# STM32.net
KiCad netlist of a schematic drawn in Altium Designer
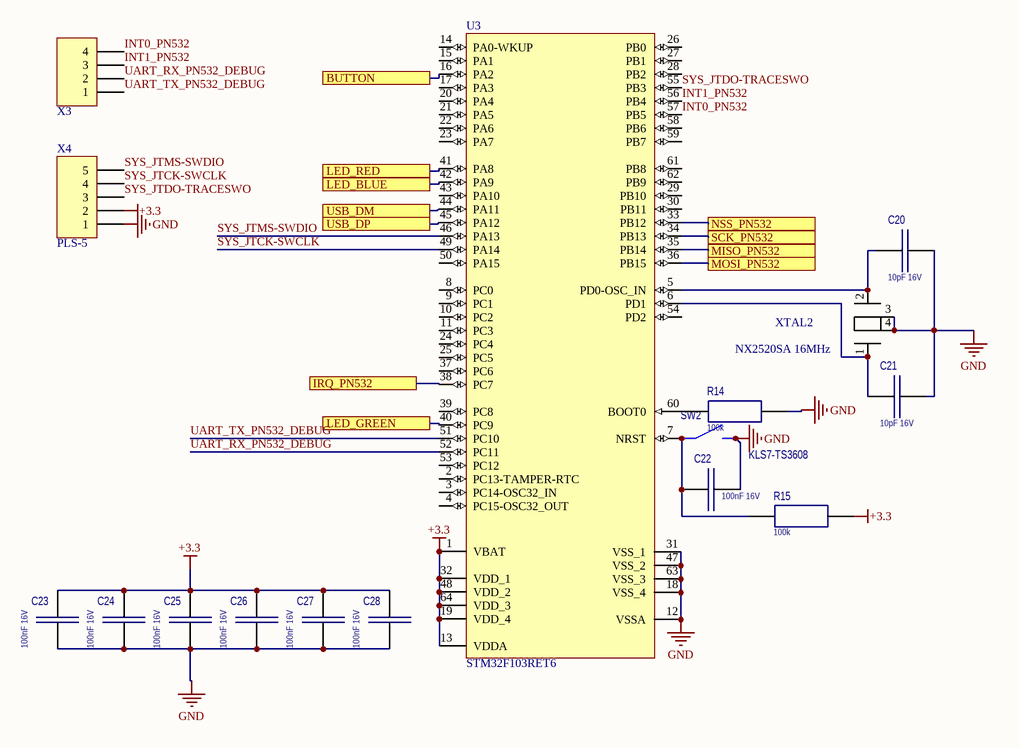
[diagram p0: STM32.SchDoc]

(export (version "E")
  (design (tool "Eeschema 10.0.6"))
  (components
    (comp (ref "C20")
      (value "10pF 16V")
      (footprint "C_0805")
      (description "Capacitor")
      (libsource (lib "AX_Altium_v2.3") (part "C0805"))
    )
    (comp (ref "C21")
      (value "10pF 16V")
      (footprint "C_0805")
      (description "Capacitor")
      (libsource (lib "AX_Altium_v2.3") (part "C0805"))
    )
    (comp (ref "C22")
      (value "100nF 16V")
      (footprint "C_0805")
      (description "Capacitor")
      (libsource (lib "AX_Altium_v2.3") (part "C0805"))
    )
    (comp (ref "C23")
      (value "100nF 16V")
      (footprint "C_0805")
      (description "Capacitor")
      (libsource (lib "AX_Altium_v2.3") (part "C0805"))
    )
    (comp (ref "C24")
      (value "100nF 16V")
      (footprint "C_0805")
      (description "Capacitor")
      (libsource (lib "AX_Altium_v2.3") (part "C0805"))
    )
    (comp (ref "C25")
      (value "100nF 16V")
      (footprint "C_0805")
      (description "Capacitor")
      (libsource (lib "AX_Altium_v2.3") (part "C0805"))
    )
    (comp (ref "C26")
      (value "100nF 16V")
      (footprint "C_0805")
      (description "Capacitor")
      (libsource (lib "AX_Altium_v2.3") (part "C0805"))
    )
    (comp (ref "C27")
      (value "100nF 16V")
      (footprint "C_0805")
      (description "Capacitor")
      (libsource (lib "AX_Altium_v2.3") (part "C0805"))
    )
    (comp (ref "C28")
      (value "100nF 16V")
      (footprint "C_0805")
      (description "Capacitor")
      (libsource (lib "AX_Altium_v2.3") (part "C0805"))
    )
    (comp (ref "R14")
      (value "100k")
      (footprint "R_0805")
      (description "Resistor")
      (libsource (lib "AX_Altium_v2.3") (part "R0805"))
    )
    (comp (ref "R15")
      (value "100k")
      (footprint "R_0805")
      (description "Resistor")
      (libsource (lib "AX_Altium_v2.3") (part "R0805"))
    )
    (comp (ref "SW2")
      (value "KLS7-TS3608")
      (footprint "KLS7-TS3611")
      (libsource (lib "ConnectorButtonSocetDisplay") (part "button"))
    )
    (comp (ref "U3")
      (value "STM32F103RET6")
      (footprint "LQFP64_L")
      (libsource (lib "AX_Altium_v2.3") (part "STM32F103RET6"))
    )
    (comp (ref "X3")
      (value "PLS-4")
      (footprint "PLS-4-3D")
      (description "Header, 4-Pin")
      (fields (field (name "PUBLISHER") "Altium Limited"))
      (libsource (lib "ConnectorButtonSocetDisplay") (part "PLS-4"))
    )
    (comp (ref "X4")
      (value "PLS-5")
      (footprint "PLS-5-3D")
      (description "Header, 5-Pin")
      (fields (field (name "PUBLISHER") "Altium Limited"))
      (libsource (lib "ConnectorButtonSocetDisplay") (part "PLS-5"))
    )
    (comp (ref "XTAL2")
      (value "NX2520SA 16MHz")
      (footprint "NX2520SA")
      (description "Quartz")
      (libsource (lib "Quartz") (part "NX2520SA"))
    )
  )
  (nets
    (net (code "1") (name "+3.3") (class "Default")
      (node (ref "C23") (pin "1") (pinfunction "1_1") (pintype "passive"))
      (node (ref "C24") (pin "1") (pinfunction "1_1") (pintype "passive"))
      (node (ref "C25") (pin "1") (pinfunction "1_1") (pintype "passive"))
      (node (ref "C26") (pin "1") (pinfunction "1_1") (pintype "passive"))
      (node (ref "C27") (pin "1") (pinfunction "1_1") (pintype "passive"))
      (node (ref "C28") (pin "1") (pinfunction "1_1") (pintype "passive"))
      (node (ref "R15") (pin "1") (pinfunction "1_1") (pintype "passive"))
      (node (ref "U3") (pin "1") (pinfunction "VBAT_1") (pintype "power_in"))
      (node (ref "U3") (pin "13") (pinfunction "VDDA_13") (pintype "power_in"))
      (node (ref "U3") (pin "19") (pinfunction "VDD_4_19") (pintype "power_in"))
      (node (ref "U3") (pin "32") (pinfunction "VDD_1_32") (pintype "power_in"))
      (node (ref "U3") (pin "48") (pinfunction "VDD_2_48") (pintype "power_in"))
      (node (ref "U3") (pin "64") (pinfunction "VDD_3_64") (pintype "power_in"))
      (node (ref "X4") (pin "2") (pinfunction "2_2") (pintype "passive"))
    )
    (net (code "2") (name "/BUTTON") (class "Default")
      (node (ref "U3") (pin "16") (pinfunction "PA2_16") (pintype "bidirectional"))
    )
    (net (code "3") (name "/INT0_PN532") (class "Default")
      (node (ref "U3") (pin "57") (pinfunction "PB5_57") (pintype "bidirectional"))
      (node (ref "X3") (pin "4") (pinfunction "4_4") (pintype "passive"))
    )
    (net (code "4") (name "/INT1_PN532") (class "Default")
      (node (ref "U3") (pin "56") (pinfunction "PB4_56") (pintype "bidirectional"))
      (node (ref "X3") (pin "3") (pinfunction "3_3") (pintype "passive"))
    )
    (net (code "5") (name "/IRQ_PN532") (class "Default")
      (node (ref "U3") (pin "38") (pinfunction "PC7_38") (pintype "bidirectional"))
    )
    (net (code "6") (name "/LED_BLUE") (class "Default")
      (node (ref "U3") (pin "42") (pinfunction "PA9_42") (pintype "bidirectional"))
    )
    (net (code "7") (name "/LED_GREEN") (class "Default")
      (node (ref "U3") (pin "40") (pinfunction "PC9_40") (pintype "bidirectional"))
    )
    (net (code "8") (name "/LED_RED") (class "Default")
      (node (ref "U3") (pin "41") (pinfunction "PA8_41") (pintype "bidirectional"))
    )
    (net (code "9") (name "/MISO_PN532") (class "Default")
      (node (ref "U3") (pin "35") (pinfunction "PB14_35") (pintype "bidirectional"))
    )
    (net (code "10") (name "/MOSI_PN532") (class "Default")
      (node (ref "U3") (pin "36") (pinfunction "PB15_36") (pintype "bidirectional"))
    )
    (net (code "11") (name "/NSS_PN532") (class "Default")
      (node (ref "U3") (pin "33") (pinfunction "PB12_33") (pintype "bidirectional"))
    )
    (net (code "12") (name "/SCK_PN532") (class "Default")
      (node (ref "U3") (pin "34") (pinfunction "PB13_34") (pintype "bidirectional"))
    )
    (net (code "13") (name "/SYS_JTCK-SWCLK") (class "Default")
      (node (ref "U3") (pin "49") (pinfunction "PA14_49") (pintype "bidirectional"))
      (node (ref "X4") (pin "4") (pinfunction "4_4") (pintype "passive"))
    )
    (net (code "14") (name "/SYS_JTDO-TRACESWO") (class "Default")
      (node (ref "U3") (pin "55") (pinfunction "PB3_55") (pintype "bidirectional"))
      (node (ref "X4") (pin "3") (pinfunction "3_3") (pintype "passive"))
    )
    (net (code "15") (name "/SYS_JTMS-SWDIO") (class "Default")
      (node (ref "U3") (pin "46") (pinfunction "PA13_46") (pintype "bidirectional"))
      (node (ref "X4") (pin "5") (pinfunction "5_5") (pintype "passive"))
    )
    (net (code "16") (name "/UART_RX_PN532_DEBUG") (class "Default")
      (node (ref "U3") (pin "52") (pinfunction "PC11_52") (pintype "bidirectional"))
      (node (ref "X3") (pin "2") (pinfunction "2_2") (pintype "passive"))
    )
    (net (code "17") (name "/UART_TX_PN532_DEBUG") (class "Default")
      (node (ref "U3") (pin "51") (pinfunction "PC10_51") (pintype "bidirectional"))
      (node (ref "X3") (pin "1") (pinfunction "1_1") (pintype "passive"))
    )
    (net (code "18") (name "/USB_DM") (class "Default")
      (node (ref "U3") (pin "44") (pinfunction "PA11_44") (pintype "bidirectional"))
    )
    (net (code "19") (name "/USB_DP") (class "Default")
      (node (ref "U3") (pin "45") (pinfunction "PA12_45") (pintype "bidirectional"))
    )
    (net (code "20") (name "GND") (class "Default")
      (node (ref "C20") (pin "1") (pinfunction "1_1") (pintype "passive"))
      (node (ref "C21") (pin "1") (pinfunction "1_1") (pintype "passive"))
      (node (ref "C22") (pin "1") (pinfunction "1_1") (pintype "passive"))
      (node (ref "C23") (pin "2") (pinfunction "2_2") (pintype "passive"))
      (node (ref "C24") (pin "2") (pinfunction "2_2") (pintype "passive"))
      (node (ref "C25") (pin "2") (pinfunction "2_2") (pintype "passive"))
      (node (ref "C26") (pin "2") (pinfunction "2_2") (pintype "passive"))
      (node (ref "C27") (pin "2") (pinfunction "2_2") (pintype "passive"))
      (node (ref "C28") (pin "2") (pinfunction "2_2") (pintype "passive"))
      (node (ref "R14") (pin "1") (pinfunction "1_1") (pintype "passive"))
      (node (ref "SW2") (pin "2") (pinfunction "2_2") (pintype "passive"))
      (node (ref "U3") (pin "12") (pinfunction "VSSA_12") (pintype "power_in"))
      (node (ref "U3") (pin "18") (pinfunction "VSS_4_18") (pintype "power_in"))
      (node (ref "U3") (pin "31") (pinfunction "VSS_1_31") (pintype "power_in"))
      (node (ref "U3") (pin "47") (pinfunction "VSS_2_47") (pintype "power_in"))
      (node (ref "U3") (pin "63") (pinfunction "VSS_3_63") (pintype "power_in"))
      (node (ref "X4") (pin "1") (pinfunction "1_1") (pintype "passive"))
      (node (ref "XTAL2") (pin "3") (pintype "passive"))
      (node (ref "XTAL2") (pin "4") (pintype "passive"))
    )
    (net (code "21") (name "Net-(U3-BOOT0)") (class "Default")
      (node (ref "R14") (pin "2") (pinfunction "2_2") (pintype "passive"))
      (node (ref "U3") (pin "60") (pinfunction "BOOT0_60") (pintype "input"))
    )
    (net (code "22") (name "Net-(U3-NRST)") (class "Default")
      (node (ref "C22") (pin "2") (pinfunction "2_2") (pintype "passive"))
      (node (ref "R15") (pin "2") (pinfunction "2_2") (pintype "passive"))
      (node (ref "SW2") (pin "1") (pinfunction "1_1") (pintype "passive"))
      (node (ref "U3") (pin "7") (pinfunction "NRST_7") (pintype "bidirectional"))
    )
    (net (code "23") (name "Net-(U3-PD0-OSC_IN)") (class "Default")
      (node (ref "C20") (pin "2") (pinfunction "2_2") (pintype "passive"))
      (node (ref "U3") (pin "5") (pinfunction "PD0-OSC_IN_5") (pintype "bidirectional"))
      (node (ref "XTAL2") (pin "2") (pintype "passive"))
    )
    (net (code "24") (name "Net-(U3-PD1)") (class "Default")
      (node (ref "C21") (pin "2") (pinfunction "2_2") (pintype "passive"))
      (node (ref "U3") (pin "6") (pinfunction "PD1_6") (pintype "bidirectional"))
      (node (ref "XTAL2") (pin "1") (pintype "passive"))
    )
    (net (code "25") (name "unconnected-(U3-PA0-WKUP-Pad14)") (class "Default")
      (node (ref "U3") (pin "14") (pinfunction "PA0-WKUP_14") (pintype "bidirectional"))
    )
    (net (code "26") (name "unconnected-(U3-PA1-Pad15)") (class "Default")
      (node (ref "U3") (pin "15") (pinfunction "PA1_15") (pintype "bidirectional"))
    )
    (net (code "27") (name "unconnected-(U3-PA3-Pad17)") (class "Default")
      (node (ref "U3") (pin "17") (pinfunction "PA3_17") (pintype "bidirectional"))
    )
    (net (code "28") (name "unconnected-(U3-PA4-Pad20)") (class "Default")
      (node (ref "U3") (pin "20") (pinfunction "PA4_20") (pintype "bidirectional"))
    )
    (net (code "29") (name "unconnected-(U3-PA5-Pad21)") (class "Default")
      (node (ref "U3") (pin "21") (pinfunction "PA5_21") (pintype "bidirectional"))
    )
    (net (code "30") (name "unconnected-(U3-PA6-Pad22)") (class "Default")
      (node (ref "U3") (pin "22") (pinfunction "PA6_22") (pintype "bidirectional"))
    )
    (net (code "31") (name "unconnected-(U3-PA7-Pad23)") (class "Default")
      (node (ref "U3") (pin "23") (pinfunction "PA7_23") (pintype "bidirectional"))
    )
    (net (code "32") (name "unconnected-(U3-PA10-Pad43)") (class "Default")
      (node (ref "U3") (pin "43") (pinfunction "PA10_43") (pintype "bidirectional"))
    )
    (net (code "33") (name "unconnected-(U3-PA15-Pad50)") (class "Default")
      (node (ref "U3") (pin "50") (pinfunction "PA15_50") (pintype "bidirectional"))
    )
    (net (code "34") (name "unconnected-(U3-PB0-Pad26)") (class "Default")
      (node (ref "U3") (pin "26") (pinfunction "PB0_26") (pintype "bidirectional"))
    )
    (net (code "35") (name "unconnected-(U3-PB1-Pad27)") (class "Default")
      (node (ref "U3") (pin "27") (pinfunction "PB1_27") (pintype "bidirectional"))
    )
    (net (code "36") (name "unconnected-(U3-PB2-Pad28)") (class "Default")
      (node (ref "U3") (pin "28") (pinfunction "PB2_28") (pintype "bidirectional"))
    )
    (net (code "37") (name "unconnected-(U3-PB6-Pad58)") (class "Default")
      (node (ref "U3") (pin "58") (pinfunction "PB6_58") (pintype "bidirectional"))
    )
    (net (code "38") (name "unconnected-(U3-PB7-Pad59)") (class "Default")
      (node (ref "U3") (pin "59") (pinfunction "PB7_59") (pintype "bidirectional"))
    )
    (net (code "39") (name "unconnected-(U3-PB8-Pad61)") (class "Default")
      (node (ref "U3") (pin "61") (pinfunction "PB8_61") (pintype "bidirectional"))
    )
    (net (code "40") (name "unconnected-(U3-PB9-Pad62)") (class "Default")
      (node (ref "U3") (pin "62") (pinfunction "PB9_62") (pintype "bidirectional"))
    )
    (net (code "41") (name "unconnected-(U3-PB10-Pad29)") (class "Default")
      (node (ref "U3") (pin "29") (pinfunction "PB10_29") (pintype "bidirectional"))
    )
    (net (code "42") (name "unconnected-(U3-PB11-Pad30)") (class "Default")
      (node (ref "U3") (pin "30") (pinfunction "PB11_30") (pintype "bidirectional"))
    )
    (net (code "43") (name "unconnected-(U3-PC0-Pad8)") (class "Default")
      (node (ref "U3") (pin "8") (pinfunction "PC0_8") (pintype "bidirectional"))
    )
    (net (code "44") (name "unconnected-(U3-PC1-Pad9)") (class "Default")
      (node (ref "U3") (pin "9") (pinfunction "PC1_9") (pintype "bidirectional"))
    )
    (net (code "45") (name "unconnected-(U3-PC2-Pad10)") (class "Default")
      (node (ref "U3") (pin "10") (pinfunction "PC2_10") (pintype "bidirectional"))
    )
    (net (code "46") (name "unconnected-(U3-PC3-Pad11)") (class "Default")
      (node (ref "U3") (pin "11") (pinfunction "PC3_11") (pintype "bidirectional"))
    )
    (net (code "47") (name "unconnected-(U3-PC4-Pad24)") (class "Default")
      (node (ref "U3") (pin "24") (pinfunction "PC4_24") (pintype "bidirectional"))
    )
    (net (code "48") (name "unconnected-(U3-PC5-Pad25)") (class "Default")
      (node (ref "U3") (pin "25") (pinfunction "PC5_25") (pintype "bidirectional"))
    )
    (net (code "49") (name "unconnected-(U3-PC6-Pad37)") (class "Default")
      (node (ref "U3") (pin "37") (pinfunction "PC6_37") (pintype "bidirectional"))
    )
    (net (code "50") (name "unconnected-(U3-PC8-Pad39)") (class "Default")
      (node (ref "U3") (pin "39") (pinfunction "PC8_39") (pintype "bidirectional"))
    )
    (net (code "51") (name "unconnected-(U3-PC12-Pad53)") (class "Default")
      (node (ref "U3") (pin "53") (pinfunction "PC12_53") (pintype "bidirectional"))
    )
    (net (code "52") (name "unconnected-(U3-PC13-TAMPER-RTC-Pad2)") (class "Default")
      (node (ref "U3") (pin "2") (pinfunction "PC13-TAMPER-RTC_2") (pintype "bidirectional"))
    )
    (net (code "53") (name "unconnected-(U3-PC14-OSC32_IN-Pad3)") (class "Default")
      (node (ref "U3") (pin "3") (pinfunction "PC14-OSC32_IN_3") (pintype "bidirectional"))
    )
    (net (code "54") (name "unconnected-(U3-PC15-OSC32_OUT-Pad4)") (class "Default")
      (node (ref "U3") (pin "4") (pinfunction "PC15-OSC32_OUT_4") (pintype "bidirectional"))
    )
    (net (code "55") (name "unconnected-(U3-PD2-Pad54)") (class "Default")
      (node (ref "U3") (pin "54") (pinfunction "PD2_54") (pintype "bidirectional"))
    )
  )
)
